# zzh-debug.net
KiCad netlist of a schematic drawn in EAGLE
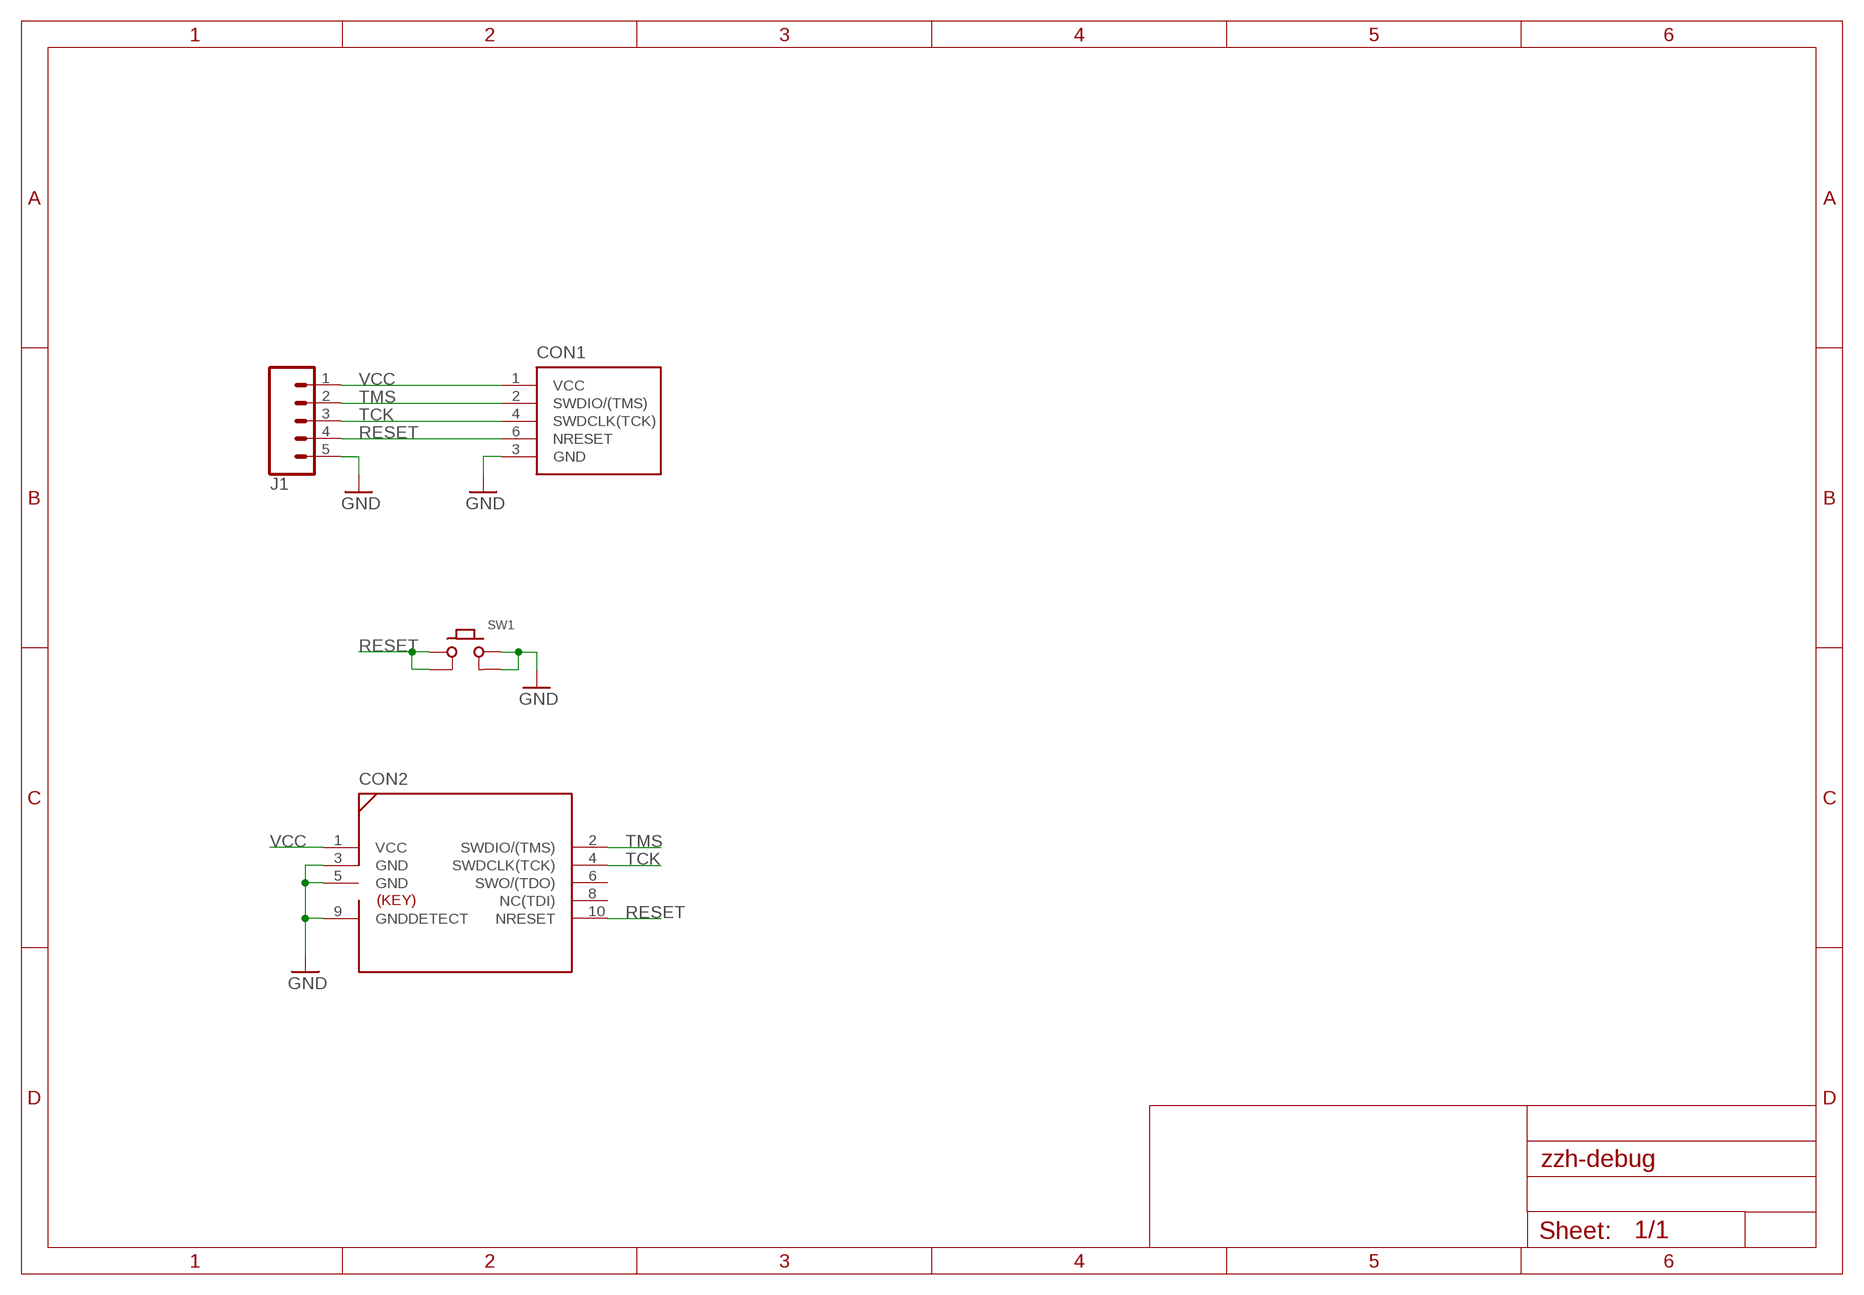
[diagram p0: schematic, sheet 1]

(export (version "E")
  (design (tool "Eeschema 10.0.6"))
  (components
    (comp (ref "CON1")
      (value "DEBUG_CORTEX-SWD-5PIN-FEMALE6")
      (footprint "eagle-import:SHENZHEN_2X3_1.27MM_TH_FEMALE")
      (libsource (lib "eagle-import") (part "DEBUG_CORTEX-SWD-5PIN-FEMALE6"))
    )
    (comp (ref "CON2")
      (value "DEBUG_CORTEX-SWD-TH")
      (footprint "eagle-import:SHENZHEN_2X5_1.27MM_TH_MALE_SHROUD")
      (libsource (lib "eagle-import") (part "DEBUG_CORTEX-SWD-TH"))
    )
    (comp (ref "J1")
      (value "CONN_05LOCK_LONGPADS")
      (footprint "eagle-import:1X05_LOCK_LONGPADS")
      (libsource (lib "eagle-import") (part "CONN_05LOCK_LONGPADS"))
    )
    (comp (ref "SW1")
      (value "PUSHBUTTON-K2-1177SW-D4DW-06")
      (footprint "eagle-import:K2-1177SW-D4DW-06")
      (libsource (lib "eagle-import") (part "PUSHBUTTON-K2-1177SW-D4DW-06"))
    )
  )
  (nets
    (net (code "1") (name "/RESET") (class "Default")
      (node (ref "CON1") (pin "6") (pinfunction "NRESET_6") (pintype "bidirectional"))
      (node (ref "CON2") (pin "10") (pinfunction "NRESET_10") (pintype "bidirectional"))
      (node (ref "J1") (pin "4") (pinfunction "4_4") (pintype "passive"))
      (node (ref "SW1") (pin "1") (pinfunction "1_1_1") (pintype "bidirectional"))
      (node (ref "SW1") (pin "2") (pinfunction "1_2_2") (pintype "bidirectional"))
    )
    (net (code "2") (name "/TCK") (class "Default")
      (node (ref "CON1") (pin "4") (pinfunction "SWDCLK(TCK)_4") (pintype "bidirectional"))
      (node (ref "CON2") (pin "4") (pinfunction "SWDCLK(TCK)_4") (pintype "bidirectional"))
      (node (ref "J1") (pin "3") (pinfunction "3_3") (pintype "passive"))
    )
    (net (code "3") (name "/TMS") (class "Default")
      (node (ref "CON1") (pin "2") (pinfunction "SWDIO/(TMS)_2") (pintype "bidirectional"))
      (node (ref "CON2") (pin "2") (pinfunction "SWDIO/(TMS)_2") (pintype "bidirectional"))
      (node (ref "J1") (pin "2") (pinfunction "2_2") (pintype "passive"))
    )
    (net (code "4") (name "/VCC") (class "Default")
      (node (ref "CON1") (pin "1") (pinfunction "VCC_1") (pintype "bidirectional"))
      (node (ref "CON2") (pin "1") (pinfunction "VCC_1") (pintype "bidirectional"))
      (node (ref "J1") (pin "1") (pinfunction "1_1") (pintype "passive"))
    )
    (net (code "5") (name "GND") (class "Default")
      (node (ref "CON1") (pin "3") (pinfunction "GND_3") (pintype "bidirectional"))
      (node (ref "CON2") (pin "3") (pinfunction "GND_3") (pintype "bidirectional"))
      (node (ref "CON2") (pin "5") (pinfunction "GND_5") (pintype "bidirectional"))
      (node (ref "CON2") (pin "9") (pinfunction "GNDDETECT_9") (pintype "bidirectional"))
      (node (ref "J1") (pin "5") (pinfunction "5_5") (pintype "passive"))
      (node (ref "SW1") (pin "3") (pinfunction "2_1_3") (pintype "bidirectional"))
      (node (ref "SW1") (pin "4") (pinfunction "2_2_4") (pintype "bidirectional"))
    )
    (net (code "6") (name "unconnected-(CON2-NC(TDI)-Pad8)") (class "Default")
      (node (ref "CON2") (pin "8") (pinfunction "NC(TDI)_8") (pintype "bidirectional"))
    )
    (net (code "7") (name "unconnected-(CON2-SWO{slash}(TDO)-Pad6)") (class "Default")
      (node (ref "CON2") (pin "6") (pinfunction "SWO/(TDO)_6") (pintype "bidirectional"))
    )
  )
)
